# pinheader_breakout.net
KiCad netlist of a schematic drawn in EAGLE
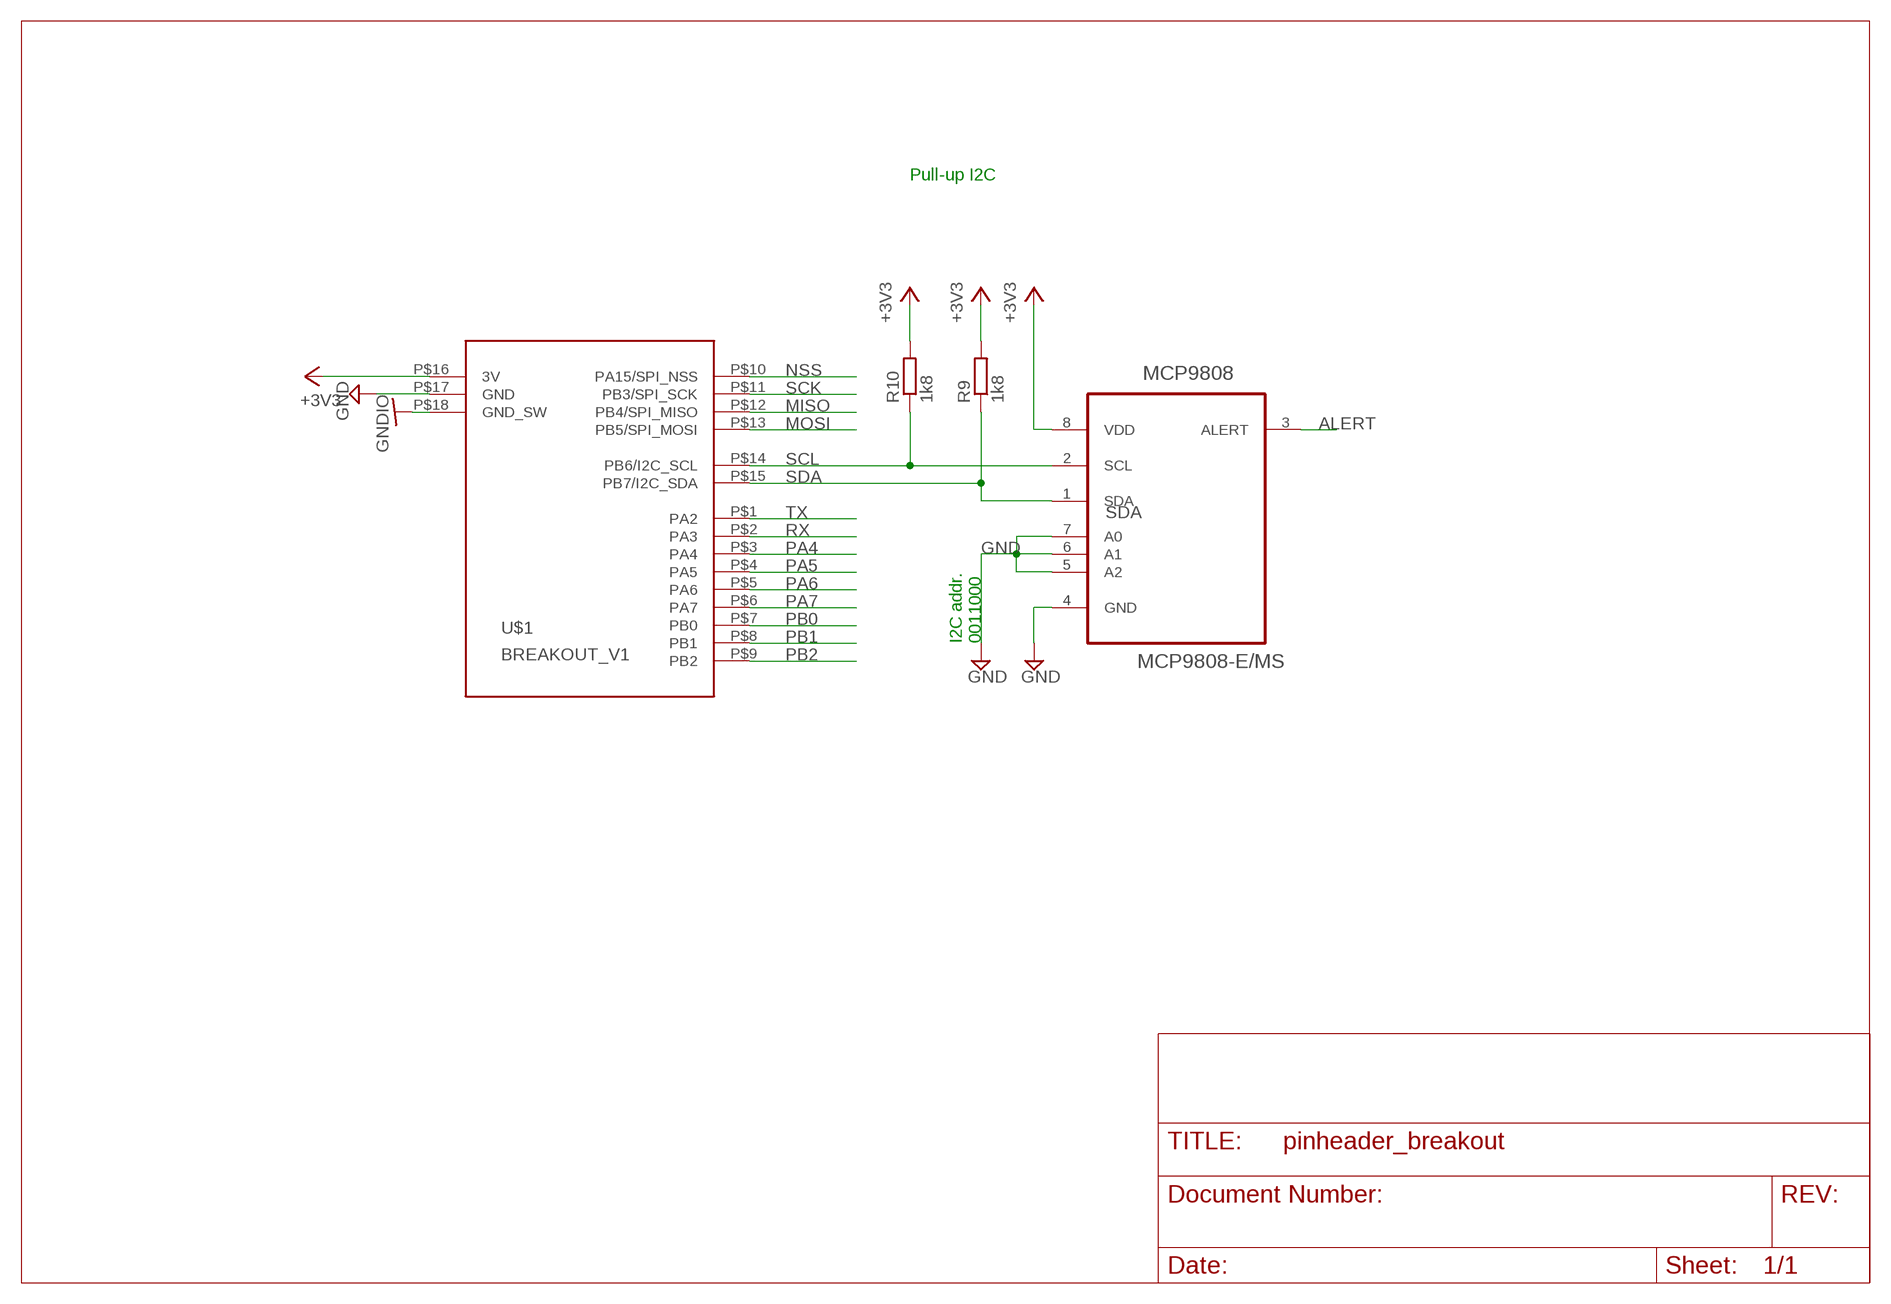
[diagram p0: schematic, sheet 1]

(export (version "E")
  (design (tool "Eeschema 10.0.6"))
  (components
    (comp (ref "MCP9808")
      (value "MCP9808-E/MS")
      (footprint "eagle-import:SOP65P490X110-8N")
      (libsource (lib "eagle-import") (part "MCP9808-E/MS"))
    )
    (comp (ref "R9")
      (value "1k8")
      (footprint "eagle-import:R0805")
      (libsource (lib "eagle-import") (part "R-EU_R0805"))
    )
    (comp (ref "R10")
      (value "1k8")
      (footprint "eagle-import:R0805")
      (libsource (lib "eagle-import") (part "R-EU_R0805"))
    )
    (comp (ref "U$1")
      (value "BREAKOUT_V1")
      (footprint "eagle-import:BREAKOUT_V1")
      (libsource (lib "eagle-import") (part "BREAKOUT_V1"))
    )
  )
  (nets
    (net (code "1") (name "+3V3") (class "Default")
      (node (ref "MCP9808") (pin "8") (pinfunction "VDD_8") (pintype "power_in"))
      (node (ref "R10") (pin "2") (pinfunction "2_2") (pintype "passive"))
      (node (ref "R9") (pin "2") (pinfunction "2_2") (pintype "passive"))
      (node (ref "U$1") (pin "P$16") (pinfunction "3V_P$16") (pintype "bidirectional"))
    )
    (net (code "2") (name "/ALERT") (class "Default")
      (node (ref "MCP9808") (pin "3") (pinfunction "ALERT_3") (pintype "output"))
    )
    (net (code "3") (name "/MISO") (class "Default")
      (node (ref "U$1") (pin "P$12") (pinfunction "PB4/SPI_MISO_P$12") (pintype "bidirectional"))
    )
    (net (code "4") (name "/MOSI") (class "Default")
      (node (ref "U$1") (pin "P$13") (pinfunction "PB5/SPI_MOSI_P$13") (pintype "bidirectional"))
    )
    (net (code "5") (name "/NSS") (class "Default")
      (node (ref "U$1") (pin "P$10") (pinfunction "PA15/SPI_NSS_P$10") (pintype "bidirectional"))
    )
    (net (code "6") (name "/PA4") (class "Default")
      (node (ref "U$1") (pin "P$3") (pinfunction "PA4_P$3") (pintype "bidirectional"))
    )
    (net (code "7") (name "/PA5") (class "Default")
      (node (ref "U$1") (pin "P$4") (pinfunction "PA5_P$4") (pintype "bidirectional"))
    )
    (net (code "8") (name "/PA6") (class "Default")
      (node (ref "U$1") (pin "P$5") (pinfunction "PA6_P$5") (pintype "bidirectional"))
    )
    (net (code "9") (name "/PA7") (class "Default")
      (node (ref "U$1") (pin "P$6") (pinfunction "PA7_P$6") (pintype "bidirectional"))
    )
    (net (code "10") (name "/PB0") (class "Default")
      (node (ref "U$1") (pin "P$7") (pinfunction "PB0_P$7") (pintype "bidirectional"))
    )
    (net (code "11") (name "/PB1") (class "Default")
      (node (ref "U$1") (pin "P$8") (pinfunction "PB1_P$8") (pintype "bidirectional"))
    )
    (net (code "12") (name "/PB2") (class "Default")
      (node (ref "U$1") (pin "P$9") (pinfunction "PB2_P$9") (pintype "bidirectional"))
    )
    (net (code "13") (name "/RX") (class "Default")
      (node (ref "U$1") (pin "P$2") (pinfunction "PA3_P$2") (pintype "bidirectional"))
    )
    (net (code "14") (name "/SCK") (class "Default")
      (node (ref "U$1") (pin "P$11") (pinfunction "PB3/SPI_SCK_P$11") (pintype "bidirectional"))
    )
    (net (code "15") (name "/SCL") (class "Default")
      (node (ref "MCP9808") (pin "2") (pinfunction "SCL_2") (pintype "input"))
      (node (ref "R10") (pin "1") (pinfunction "1_1") (pintype "passive"))
      (node (ref "U$1") (pin "P$14") (pinfunction "PB6/I2C_SCL_P$14") (pintype "bidirectional"))
    )
    (net (code "16") (name "/SDA") (class "Default")
      (node (ref "MCP9808") (pin "1") (pinfunction "SDA_1") (pintype "bidirectional"))
      (node (ref "R9") (pin "1") (pinfunction "1_1") (pintype "passive"))
      (node (ref "U$1") (pin "P$15") (pinfunction "PB7/I2C_SDA_P$15") (pintype "bidirectional"))
    )
    (net (code "17") (name "/TX") (class "Default")
      (node (ref "U$1") (pin "P$1") (pinfunction "PA2_P$1") (pintype "bidirectional"))
    )
    (net (code "18") (name "GND") (class "Default")
      (node (ref "MCP9808") (pin "4") (pinfunction "GND_4") (pintype "passive"))
      (node (ref "MCP9808") (pin "5") (pinfunction "A2_5") (pintype "input"))
      (node (ref "MCP9808") (pin "6") (pinfunction "A1_6") (pintype "input"))
      (node (ref "MCP9808") (pin "7") (pinfunction "A0_7") (pintype "input"))
      (node (ref "U$1") (pin "P$17") (pinfunction "GND_P$17") (pintype "bidirectional"))
    )
    (net (code "19") (name "GNDIO") (class "Default")
      (node (ref "U$1") (pin "P$18") (pinfunction "GND_SW_P$18") (pintype "bidirectional"))
    )
  )
)
